# pcb_univ_3-101-0-x-rev2.net
KiCad netlist of a schematic drawn in EAGLE
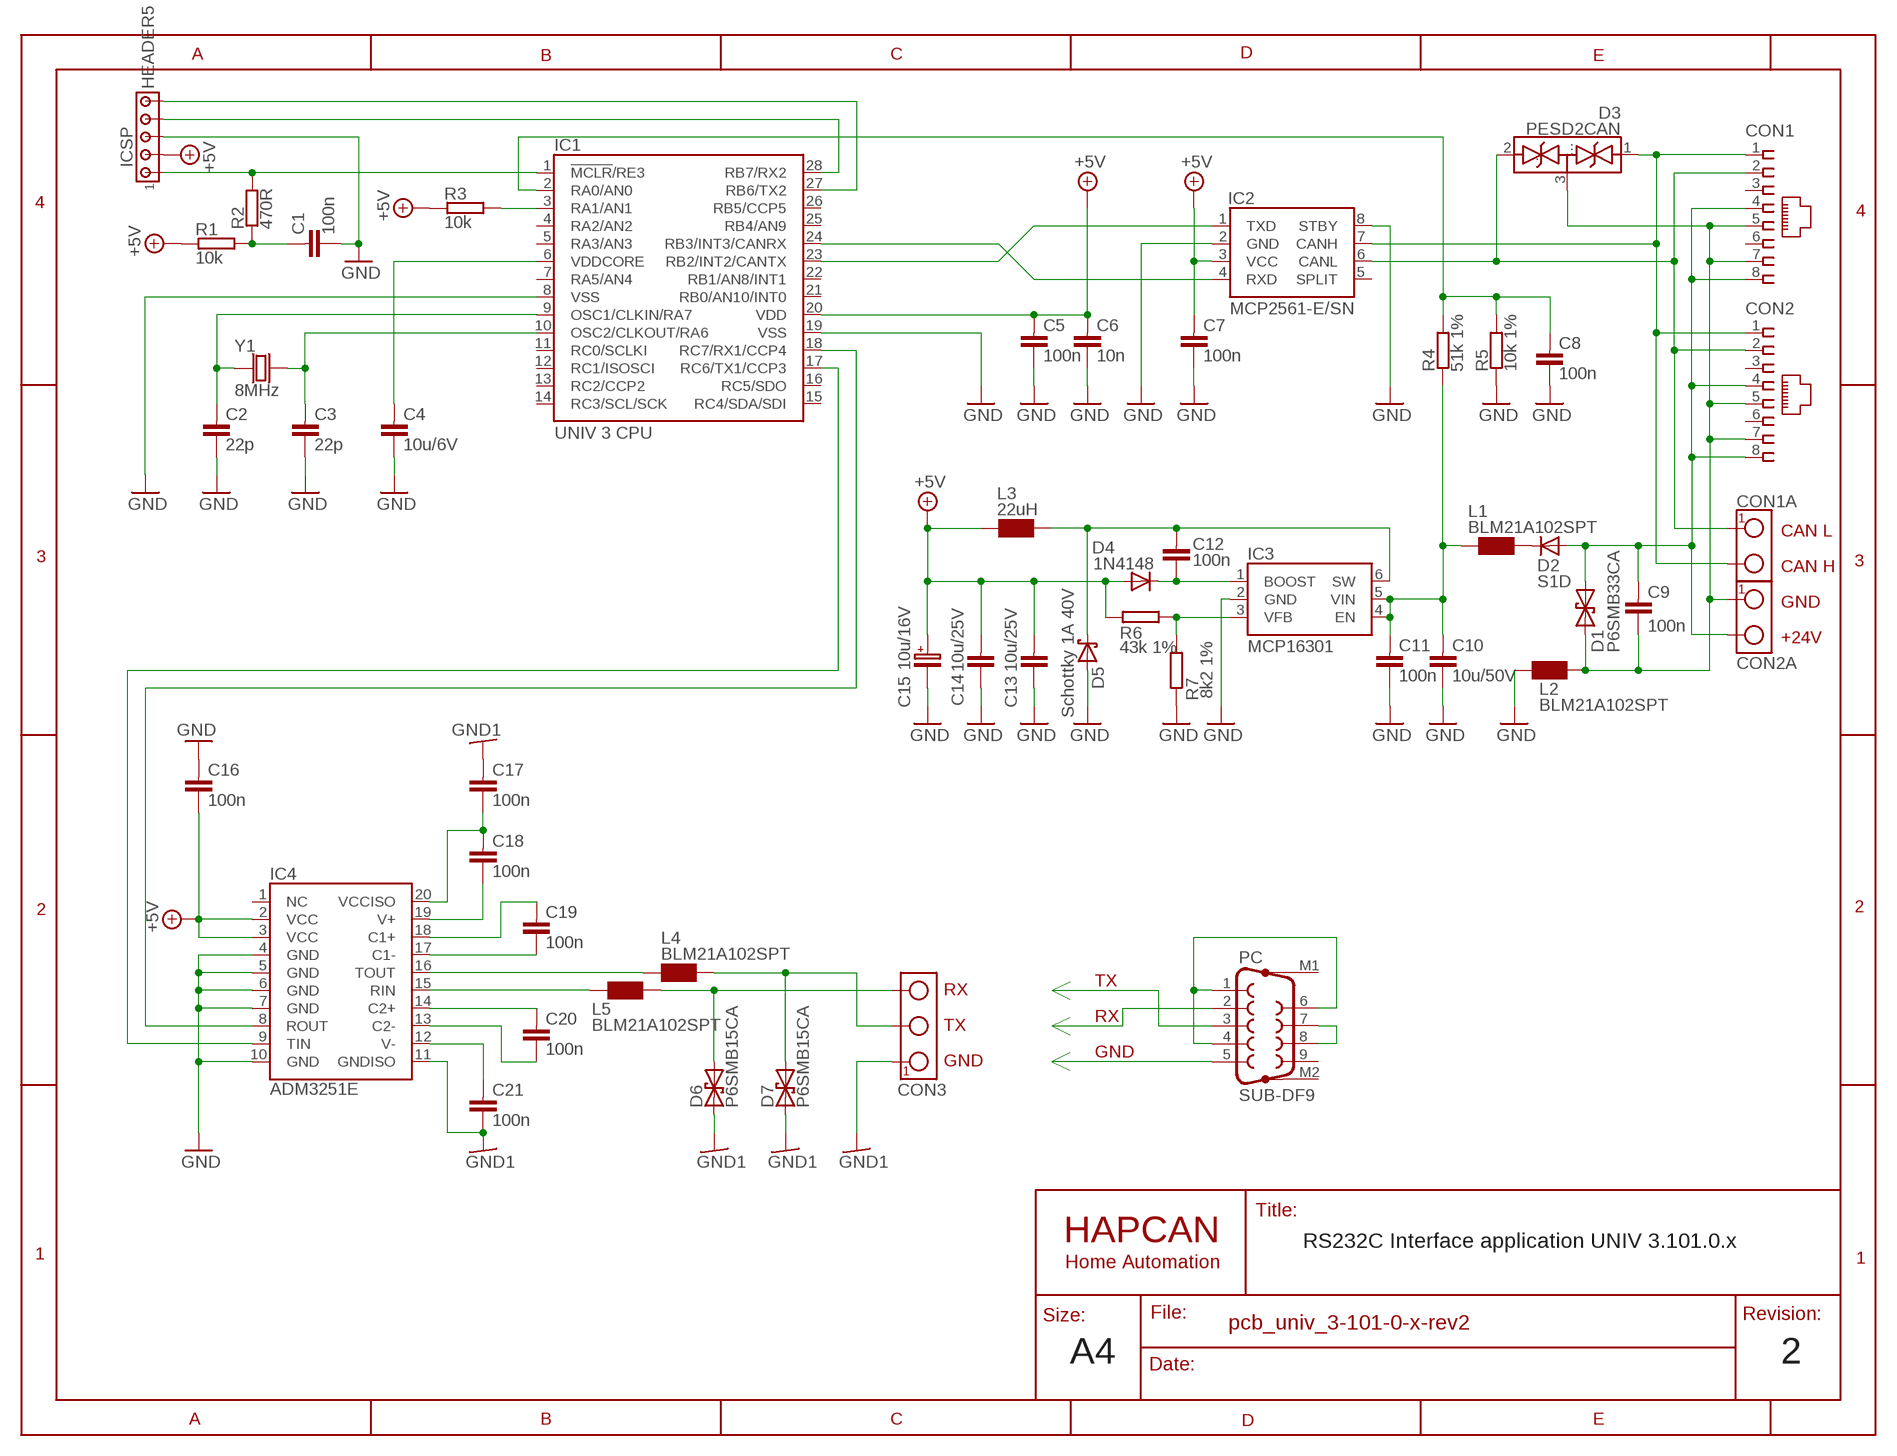
[diagram p0: schematic, sheet 1]

(export (version "E")
  (design (tool "Eeschema 10.0.6"))
  (components
    (comp (ref "C1")
      (value "100n")
      (footprint "eagle-import:0805")
      (libsource (lib "eagle-import") (part "CAPACITOR0805"))
    )
    (comp (ref "C2")
      (value "22p")
      (footprint "eagle-import:0805")
      (libsource (lib "eagle-import") (part "CAPACITOR0805"))
    )
    (comp (ref "C3")
      (value "22p")
      (footprint "eagle-import:0805")
      (libsource (lib "eagle-import") (part "CAPACITOR0805"))
    )
    (comp (ref "C4")
      (value "10u/6V")
      (footprint "eagle-import:0805")
      (libsource (lib "eagle-import") (part "CAPACITOR0805"))
    )
    (comp (ref "C5")
      (value "100n")
      (footprint "eagle-import:0805")
      (libsource (lib "eagle-import") (part "CAPACITOR0805"))
    )
    (comp (ref "C6")
      (value "10n")
      (footprint "eagle-import:0805")
      (libsource (lib "eagle-import") (part "CAPACITOR0805"))
    )
    (comp (ref "C7")
      (value "100n")
      (footprint "eagle-import:0805")
      (libsource (lib "eagle-import") (part "CAPACITOR0805"))
    )
    (comp (ref "C8")
      (value "100n")
      (footprint "eagle-import:0805")
      (libsource (lib "eagle-import") (part "CAPACITOR0805"))
    )
    (comp (ref "C9")
      (value "100n")
      (footprint "eagle-import:0805")
      (libsource (lib "eagle-import") (part "CAPACITOR0805"))
    )
    (comp (ref "C10")
      (value "10u/50V")
      (footprint "eagle-import:1210")
      (libsource (lib "eagle-import") (part "CAPACITOR1210"))
    )
    (comp (ref "C11")
      (value "100n")
      (footprint "eagle-import:0805")
      (libsource (lib "eagle-import") (part "CAPACITOR0805"))
    )
    (comp (ref "C12")
      (value "100n")
      (footprint "eagle-import:0805")
      (libsource (lib "eagle-import") (part "CAPACITOR0805"))
    )
    (comp (ref "C13")
      (value "10u/25V")
      (footprint "eagle-import:1206")
      (libsource (lib "eagle-import") (part "CAPACITOR1206"))
    )
    (comp (ref "C14")
      (value "10u/25V")
      (footprint "eagle-import:1206")
      (libsource (lib "eagle-import") (part "CAPACITOR1206"))
    )
    (comp (ref "C15")
      (value "10u/16V")
      (footprint "eagle-import:SMC_B")
      (libsource (lib "eagle-import") (part "CAPACITOR-POLARIZED-SMC_B"))
    )
    (comp (ref "C16")
      (value "100n")
      (footprint "eagle-import:0805")
      (libsource (lib "eagle-import") (part "CAPACITOR0805"))
    )
    (comp (ref "C17")
      (value "100n")
      (footprint "eagle-import:0805")
      (libsource (lib "eagle-import") (part "CAPACITOR0805"))
    )
    (comp (ref "C18")
      (value "100n")
      (footprint "eagle-import:0805")
      (libsource (lib "eagle-import") (part "CAPACITOR0805"))
    )
    (comp (ref "C19")
      (value "100n")
      (footprint "eagle-import:0805")
      (libsource (lib "eagle-import") (part "CAPACITOR0805"))
    )
    (comp (ref "C20")
      (value "100n")
      (footprint "eagle-import:0805")
      (libsource (lib "eagle-import") (part "CAPACITOR0805"))
    )
    (comp (ref "C21")
      (value "100n")
      (footprint "eagle-import:0805")
      (libsource (lib "eagle-import") (part "CAPACITOR0805"))
    )
    (comp (ref "CON1")
      (value "RJ45-SOCKET")
      (footprint "eagle-import:RJ45-PCB-SOCKET")
      (libsource (lib "eagle-import") (part "RJ45-SOCKET"))
    )
    (comp (ref "CON1A")
      (value "TERMINAL-2")
      (footprint "eagle-import:ARK2-5X10,5MM")
      (libsource (lib "eagle-import") (part "TERMINAL-2-5X10,5MM"))
    )
    (comp (ref "CON2")
      (value "RJ45-SOCKET")
      (footprint "eagle-import:RJ45-PCB-SOCKET")
      (libsource (lib "eagle-import") (part "RJ45-SOCKET"))
    )
    (comp (ref "CON2A")
      (value "TERMINAL-2")
      (footprint "eagle-import:ARK2-5X10,5MM")
      (libsource (lib "eagle-import") (part "TERMINAL-2-5X10,5MM"))
    )
    (comp (ref "CON3")
      (value "TERMINAL-3-5X10.5MM")
      (footprint "eagle-import:ARK3-5X10.5MM")
      (libsource (lib "eagle-import") (part "TERMINAL-3-5X10.5MM"))
    )
    (comp (ref "D1")
      (value "P6SMB33CA")
      (footprint "eagle-import:DO-214_TRANSIL2")
      (libsource (lib "eagle-import") (part "DIODE_TRANSIL2"))
    )
    (comp (ref "D2")
      (value "S1D")
      (footprint "eagle-import:DO-214")
      (libsource (lib "eagle-import") (part "DIODE_DO-214"))
    )
    (comp (ref "D3")
      (value "PESD2CAN")
      (footprint "eagle-import:SOT-23")
      (libsource (lib "eagle-import") (part "PESD2CANSOT-23"))
    )
    (comp (ref "D4")
      (value "1N4148")
      (footprint "eagle-import:0805")
      (libsource (lib "eagle-import") (part "DIODE_0805"))
    )
    (comp (ref "D5")
      (value "Schottky 1A 40V")
      (footprint "eagle-import:DO-214")
      (libsource (lib "eagle-import") (part "DIODE_TRANSIL1_DO214"))
    )
    (comp (ref "D6")
      (value "P6SMB15CA")
      (footprint "eagle-import:DO-214_TRANSIL2")
      (libsource (lib "eagle-import") (part "DIODE_TRANSIL2"))
    )
    (comp (ref "D7")
      (value "P6SMB15CA")
      (footprint "eagle-import:DO-214_TRANSIL2")
      (libsource (lib "eagle-import") (part "DIODE_TRANSIL2"))
    )
    (comp (ref "IC1")
      (value "UNIV 3 CPU")
      (footprint "eagle-import:UNIV3CPU")
      (libsource (lib "eagle-import") (part "UNIV3CPU-I/SO"))
    )
    (comp (ref "IC2")
      (value "MCP2561-E/SN")
      (footprint "eagle-import:SO-08")
      (libsource (lib "eagle-import") (part "MCP2561-E/SN"))
    )
    (comp (ref "IC3")
      (value "MCP16301")
      (footprint "eagle-import:SOT-23-6")
      (libsource (lib "eagle-import") (part "MCP16301SOT23-6"))
    )
    (comp (ref "IC4")
      (value "ADM3251E")
      (footprint "eagle-import:SO-20W")
      (libsource (lib "eagle-import") (part "ADM3251E"))
    )
    (comp (ref "ICSP")
      (value "HEADER5")
      (footprint "eagle-import:SIP-5")
      (libsource (lib "eagle-import") (part "HEADER5"))
    )
    (comp (ref "L1")
      (value "BLM21A102SPT")
      (footprint "eagle-import:0805")
      (libsource (lib "eagle-import") (part "CHOKE0805"))
    )
    (comp (ref "L2")
      (value "BLM21A102SPT")
      (footprint "eagle-import:0805")
      (libsource (lib "eagle-import") (part "CHOKE0805"))
    )
    (comp (ref "L3")
      (value "22uH")
      (footprint "eagle-import:CHOKE-DER0705")
      (libsource (lib "eagle-import") (part "CHOKEDER0705"))
    )
    (comp (ref "L4")
      (value "BLM21A102SPT")
      (footprint "eagle-import:0805")
      (libsource (lib "eagle-import") (part "CHOKE0805"))
    )
    (comp (ref "L5")
      (value "BLM21A102SPT")
      (footprint "eagle-import:0805")
      (libsource (lib "eagle-import") (part "CHOKE0805"))
    )
    (comp (ref "PC")
      (value "SUB-DF9")
      (footprint "eagle-import:SUB-D9FH-7.2MM")
      (libsource (lib "eagle-import") (part "SUB-DF9"))
    )
    (comp (ref "R1")
      (value "10k")
      (footprint "eagle-import:0805")
      (libsource (lib "eagle-import") (part "RESISTOR0805"))
    )
    (comp (ref "R2")
      (value "470R")
      (footprint "eagle-import:0805")
      (libsource (lib "eagle-import") (part "RESISTOR0805"))
    )
    (comp (ref "R3")
      (value "10k")
      (footprint "eagle-import:0805")
      (libsource (lib "eagle-import") (part "RESISTOR0805"))
    )
    (comp (ref "R4")
      (value "51k 1%")
      (footprint "eagle-import:0805")
      (libsource (lib "eagle-import") (part "RESISTOR0805"))
    )
    (comp (ref "R5")
      (value "10k 1%")
      (footprint "eagle-import:0805")
      (libsource (lib "eagle-import") (part "RESISTOR0805"))
    )
    (comp (ref "R6")
      (value "43k 1%")
      (footprint "eagle-import:0805")
      (libsource (lib "eagle-import") (part "RESISTOR0805"))
    )
    (comp (ref "R7")
      (value "8k2 1%")
      (footprint "eagle-import:0805")
      (libsource (lib "eagle-import") (part "RESISTOR0805"))
    )
    (comp (ref "Y1")
      (value "8MHz")
      (footprint "eagle-import:CRYSTAL-HC49V")
      (libsource (lib "eagle-import") (part "CRYSTAL-HC49V"))
    )
  )
  (nets
    (net (code "1") (name "+5V") (class "Default")
      (node (ref "C13") (pin "1") (pinfunction "1_1") (pintype "passive"))
      (node (ref "C14") (pin "1") (pinfunction "1_1") (pintype "passive"))
      (node (ref "C15") (pin "+") (pinfunction "1_+") (pintype "passive"))
      (node (ref "C16") (pin "2") (pinfunction "2_2") (pintype "passive"))
      (node (ref "C5") (pin "1") (pinfunction "1_1") (pintype "passive"))
      (node (ref "C6") (pin "1") (pinfunction "1_1") (pintype "passive"))
      (node (ref "C7") (pin "1") (pinfunction "1_1") (pintype "passive"))
      (node (ref "D4") (pin "2") (pinfunction "A_2") (pintype "passive"))
      (node (ref "IC1") (pin "20") (pinfunction "VDD_20") (pintype "bidirectional"))
      (node (ref "IC2") (pin "3") (pinfunction "VCC_3") (pintype "bidirectional"))
      (node (ref "IC4") (pin "2") (pinfunction "VCC_2") (pintype "bidirectional"))
      (node (ref "IC4") (pin "3") (pinfunction "VCC_3") (pintype "bidirectional"))
      (node (ref "ICSP") (pin "2") (pinfunction "2_2") (pintype "passive"))
      (node (ref "L3") (pin "1") (pinfunction "1_1") (pintype "passive"))
      (node (ref "R1") (pin "1") (pinfunction "1_1") (pintype "passive"))
      (node (ref "R3") (pin "1") (pinfunction "1_1") (pintype "passive"))
      (node (ref "R6") (pin "1") (pinfunction "1_1") (pintype "passive"))
    )
    (net (code "2") (name "GND") (class "Default")
      (node (ref "C1") (pin "2") (pinfunction "2_2") (pintype "passive"))
      (node (ref "C10") (pin "2") (pinfunction "2_2") (pintype "passive"))
      (node (ref "C11") (pin "2") (pinfunction "2_2") (pintype "passive"))
      (node (ref "C13") (pin "2") (pinfunction "2_2") (pintype "passive"))
      (node (ref "C14") (pin "2") (pinfunction "2_2") (pintype "passive"))
      (node (ref "C15") (pin "-") (pinfunction "2_-") (pintype "passive"))
      (node (ref "C16") (pin "1") (pinfunction "1_1") (pintype "passive"))
      (node (ref "C2") (pin "2") (pinfunction "2_2") (pintype "passive"))
      (node (ref "C3") (pin "2") (pinfunction "2_2") (pintype "passive"))
      (node (ref "C4") (pin "2") (pinfunction "2_2") (pintype "passive"))
      (node (ref "C5") (pin "2") (pinfunction "2_2") (pintype "passive"))
      (node (ref "C6") (pin "2") (pinfunction "2_2") (pintype "passive"))
      (node (ref "C7") (pin "2") (pinfunction "2_2") (pintype "passive"))
      (node (ref "C8") (pin "2") (pinfunction "2_2") (pintype "passive"))
      (node (ref "D5") (pin "A") (pinfunction "A_A") (pintype "passive"))
      (node (ref "IC1") (pin "19") (pinfunction "VSS_19") (pintype "bidirectional"))
      (node (ref "IC1") (pin "8") (pinfunction "VSS_8") (pintype "bidirectional"))
      (node (ref "IC2") (pin "2") (pinfunction "GND_2") (pintype "bidirectional"))
      (node (ref "IC2") (pin "8") (pinfunction "STBY_8") (pintype "bidirectional"))
      (node (ref "IC3") (pin "2") (pinfunction "GND_2") (pintype "bidirectional"))
      (node (ref "IC4") (pin "10") (pinfunction "GND_10") (pintype "bidirectional"))
      (node (ref "IC4") (pin "4") (pinfunction "GND_4") (pintype "bidirectional"))
      (node (ref "IC4") (pin "5") (pinfunction "GND_5") (pintype "bidirectional"))
      (node (ref "IC4") (pin "6") (pinfunction "GND_6") (pintype "bidirectional"))
      (node (ref "IC4") (pin "7") (pinfunction "GND_7") (pintype "bidirectional"))
      (node (ref "ICSP") (pin "3") (pinfunction "3_3") (pintype "passive"))
      (node (ref "L2") (pin "1") (pinfunction "1_1") (pintype "passive"))
      (node (ref "R5") (pin "1") (pinfunction "1_1") (pintype "passive"))
      (node (ref "R7") (pin "1") (pinfunction "1_1") (pintype "passive"))
    )
    (net (code "3") (name "GND1") (class "Default")
      (node (ref "C17") (pin "1") (pinfunction "1_1") (pintype "passive"))
      (node (ref "C21") (pin "2") (pinfunction "2_2") (pintype "passive"))
      (node (ref "CON3") (pin "1") (pinfunction "1_1") (pintype "passive"))
      (node (ref "D6") (pin "C") (pinfunction "2_C") (pintype "passive"))
      (node (ref "D7") (pin "C") (pinfunction "2_C") (pintype "passive"))
      (node (ref "IC4") (pin "11") (pinfunction "GNDISO_11") (pintype "bidirectional"))
    )
    (net (code "4") (name "Net-(C1-Pad1)") (class "Default")
      (node (ref "C1") (pin "1") (pinfunction "1_1") (pintype "passive"))
      (node (ref "R1") (pin "2") (pinfunction "2_2") (pintype "passive"))
      (node (ref "R2") (pin "1") (pinfunction "1_1") (pintype "passive"))
    )
    (net (code "5") (name "Net-(D1-1)") (class "Default")
      (node (ref "C9") (pin "1") (pinfunction "1_1") (pintype "passive"))
      (node (ref "CON1") (pin "4") (pinfunction "4_4") (pintype "passive"))
      (node (ref "CON1") (pin "8") (pinfunction "8_8") (pintype "passive"))
      (node (ref "CON2") (pin "4") (pinfunction "4_4") (pintype "passive"))
      (node (ref "CON2") (pin "8") (pinfunction "8_8") (pintype "passive"))
      (node (ref "CON2A") (pin "2") (pinfunction "2_2") (pintype "passive"))
      (node (ref "D1") (pin "A") (pinfunction "1_A") (pintype "passive"))
      (node (ref "D2") (pin "A") (pinfunction "A_A") (pintype "passive"))
    )
    (net (code "6") (name "Net-(D1-2)") (class "Default")
      (node (ref "C9") (pin "2") (pinfunction "2_2") (pintype "passive"))
      (node (ref "CON1") (pin "5") (pinfunction "5_5") (pintype "passive"))
      (node (ref "CON1") (pin "7") (pinfunction "7_7") (pintype "passive"))
      (node (ref "CON2") (pin "5") (pinfunction "5_5") (pintype "passive"))
      (node (ref "CON2") (pin "7") (pinfunction "7_7") (pintype "passive"))
      (node (ref "CON2A") (pin "1") (pinfunction "1_1") (pintype "passive"))
      (node (ref "D1") (pin "C") (pinfunction "2_C") (pintype "passive"))
      (node (ref "D3") (pin "3") (pinfunction "..._3") (pintype "bidirectional"))
      (node (ref "L2") (pin "2") (pinfunction "2_2") (pintype "passive"))
    )
    (net (code "7") (name "Net-(D2-PadC)") (class "Default")
      (node (ref "D2") (pin "C") (pinfunction "C_C") (pintype "passive"))
      (node (ref "L1") (pin "2") (pinfunction "2_2") (pintype "passive"))
    )
    (net (code "8") (name "Net-(D3-.)") (class "Default")
      (node (ref "CON1") (pin "1") (pinfunction "1_1") (pintype "passive"))
      (node (ref "CON1A") (pin "2") (pinfunction "2_2") (pintype "passive"))
      (node (ref "CON2") (pin "1") (pinfunction "1_1") (pintype "passive"))
      (node (ref "D3") (pin "1") (pinfunction "._1") (pintype "bidirectional"))
      (node (ref "IC2") (pin "7") (pinfunction "CANH_7") (pintype "bidirectional"))
    )
    (net (code "9") (name "Net-(D3-..)") (class "Default")
      (node (ref "CON1") (pin "2") (pinfunction "2_2") (pintype "passive"))
      (node (ref "CON1A") (pin "1") (pinfunction "1_1") (pintype "passive"))
      (node (ref "CON2") (pin "2") (pinfunction "2_2") (pintype "passive"))
      (node (ref "D3") (pin "2") (pinfunction ".._2") (pintype "bidirectional"))
      (node (ref "IC2") (pin "6") (pinfunction "CANL_6") (pintype "bidirectional"))
    )
    (net (code "10") (name "Net-(D4-C)") (class "Default")
      (node (ref "C12") (pin "2") (pinfunction "2_2") (pintype "passive"))
      (node (ref "D4") (pin "1") (pinfunction "C_1") (pintype "passive"))
      (node (ref "IC3") (pin "1") (pinfunction "BOOST_1") (pintype "bidirectional"))
    )
    (net (code "11") (name "Net-(D6-1)") (class "Default")
      (node (ref "CON3") (pin "3") (pinfunction "3_3") (pintype "passive"))
      (node (ref "D6") (pin "A") (pinfunction "1_A") (pintype "passive"))
      (node (ref "L5") (pin "1") (pinfunction "1_1") (pintype "passive"))
    )
    (net (code "12") (name "Net-(D7-1)") (class "Default")
      (node (ref "CON3") (pin "2") (pinfunction "2_2") (pintype "passive"))
      (node (ref "D7") (pin "A") (pinfunction "1_A") (pintype "passive"))
      (node (ref "L4") (pin "1") (pinfunction "1_1") (pintype "passive"))
    )
    (net (code "13") (name "Net-(IC1-OSC1{slash}CLKIN{slash}RA7)") (class "Default")
      (node (ref "C2") (pin "1") (pinfunction "1_1") (pintype "passive"))
      (node (ref "IC1") (pin "9") (pinfunction "OSC1/CLKIN/RA7_9") (pintype "bidirectional"))
      (node (ref "Y1") (pin "1") (pinfunction "1_1") (pintype "passive"))
    )
    (net (code "14") (name "Net-(IC1-OSC2{slash}CLKOUT{slash}RA6)") (class "Default")
      (node (ref "C3") (pin "1") (pinfunction "1_1") (pintype "passive"))
      (node (ref "IC1") (pin "10") (pinfunction "OSC2/CLKOUT/RA6_10") (pintype "bidirectional"))
      (node (ref "Y1") (pin "2") (pinfunction "2_2") (pintype "passive"))
    )
    (net (code "15") (name "Net-(IC1-RA0{slash}AN0)") (class "Default")
      (node (ref "C8") (pin "1") (pinfunction "1_1") (pintype "passive"))
      (node (ref "IC1") (pin "2") (pinfunction "RA0/AN0_2") (pintype "bidirectional"))
      (node (ref "R4") (pin "2") (pinfunction "2_2") (pintype "passive"))
      (node (ref "R5") (pin "2") (pinfunction "2_2") (pintype "passive"))
    )
    (net (code "16") (name "Net-(IC1-RA1{slash}AN1)") (class "Default")
      (node (ref "IC1") (pin "3") (pinfunction "RA1/AN1_3") (pintype "bidirectional"))
      (node (ref "R3") (pin "2") (pinfunction "2_2") (pintype "passive"))
    )
    (net (code "17") (name "Net-(IC1-RB2{slash}INT2{slash}CANTX)") (class "Default")
      (node (ref "IC1") (pin "23") (pinfunction "RB2/INT2/CANTX_23") (pintype "bidirectional"))
      (node (ref "IC2") (pin "1") (pinfunction "TXD_1") (pintype "bidirectional"))
    )
    (net (code "18") (name "Net-(IC1-RB3{slash}INT3{slash}CANRX)") (class "Default")
      (node (ref "IC1") (pin "24") (pinfunction "RB3/INT3/CANRX_24") (pintype "bidirectional"))
      (node (ref "IC2") (pin "4") (pinfunction "RXD_4") (pintype "bidirectional"))
    )
    (net (code "19") (name "Net-(IC1-RB6{slash}TX2)") (class "Default")
      (node (ref "IC1") (pin "27") (pinfunction "RB6/TX2_27") (pintype "bidirectional"))
      (node (ref "ICSP") (pin "5") (pinfunction "5_5") (pintype "passive"))
    )
    (net (code "20") (name "Net-(IC1-RB7{slash}RX2)") (class "Default")
      (node (ref "IC1") (pin "28") (pinfunction "RB7/RX2_28") (pintype "bidirectional"))
      (node (ref "ICSP") (pin "4") (pinfunction "4_4") (pintype "passive"))
    )
    (net (code "21") (name "Net-(IC1-RC6{slash}TX1{slash}CCP3)") (class "Default")
      (node (ref "IC1") (pin "17") (pinfunction "RC6/TX1/CCP3_17") (pintype "bidirectional"))
      (node (ref "IC4") (pin "9") (pinfunction "TIN_9") (pintype "bidirectional"))
    )
    (net (code "22") (name "Net-(IC1-RC7{slash}RX1{slash}CCP4)") (class "Default")
      (node (ref "IC1") (pin "18") (pinfunction "RC7/RX1/CCP4_18") (pintype "bidirectional"))
      (node (ref "IC4") (pin "8") (pinfunction "ROUT_8") (pintype "bidirectional"))
    )
    (net (code "23") (name "Net-(IC1-VDDCORE)") (class "Default")
      (node (ref "C4") (pin "1") (pinfunction "1_1") (pintype "passive"))
      (node (ref "IC1") (pin "6") (pinfunction "VDDCORE_6") (pintype "bidirectional"))
    )
    (net (code "24") (name "Net-(IC1-~{MCLR}{slash}RE3)") (class "Default")
      (node (ref "IC1") (pin "1") (pinfunction "~{MCLR}/RE3_1") (pintype "bidirectional"))
      (node (ref "ICSP") (pin "1") (pinfunction "1_1") (pintype "passive"))
      (node (ref "R2") (pin "2") (pinfunction "2_2") (pintype "passive"))
    )
    (net (code "25") (name "Net-(IC3-EN)") (class "Default")
      (node (ref "C10") (pin "1") (pinfunction "1_1") (pintype "passive"))
      (node (ref "C11") (pin "1") (pinfunction "1_1") (pintype "passive"))
      (node (ref "IC3") (pin "4") (pinfunction "EN_4") (pintype "bidirectional"))
      (node (ref "IC3") (pin "5") (pinfunction "VIN_5") (pintype "bidirectional"))
      (node (ref "L1") (pin "1") (pinfunction "1_1") (pintype "passive"))
      (node (ref "R4") (pin "1") (pinfunction "1_1") (pintype "passive"))
    )
    (net (code "26") (name "Net-(IC3-SW)") (class "Default")
      (node (ref "C12") (pin "1") (pinfunction "1_1") (pintype "passive"))
      (node (ref "D5") (pin "C") (pinfunction "C_C") (pintype "passive"))
      (node (ref "IC3") (pin "6") (pinfunction "SW_6") (pintype "bidirectional"))
      (node (ref "L3") (pin "2") (pinfunction "2_2") (pintype "passive"))
    )
    (net (code "27") (name "Net-(IC3-VFB)") (class "Default")
      (node (ref "IC3") (pin "3") (pinfunction "VFB_3") (pintype "bidirectional"))
      (node (ref "R6") (pin "2") (pinfunction "2_2") (pintype "passive"))
      (node (ref "R7") (pin "2") (pinfunction "2_2") (pintype "passive"))
    )
    (net (code "28") (name "Net-(IC4-C1+)") (class "Default")
      (node (ref "C19") (pin "1") (pinfunction "1_1") (pintype "passive"))
      (node (ref "IC4") (pin "18") (pinfunction "C1+_18") (pintype "bidirectional"))
    )
    (net (code "29") (name "Net-(IC4-C1-)") (class "Default")
      (node (ref "C19") (pin "2") (pinfunction "2_2") (pintype "passive"))
      (node (ref "IC4") (pin "17") (pinfunction "C1-_17") (pintype "bidirectional"))
    )
    (net (code "30") (name "Net-(IC4-C2+)") (class "Default")
      (node (ref "C20") (pin "1") (pinfunction "1_1") (pintype "passive"))
      (node (ref "IC4") (pin "14") (pinfunction "C2+_14") (pintype "bidirectional"))
    )
    (net (code "31") (name "Net-(IC4-C2-)") (class "Default")
      (node (ref "C20") (pin "2") (pinfunction "2_2") (pintype "passive"))
      (node (ref "IC4") (pin "13") (pinfunction "C2-_13") (pintype "bidirectional"))
    )
    (net (code "32") (name "Net-(IC4-RIN)") (class "Default")
      (node (ref "IC4") (pin "15") (pinfunction "RIN_15") (pintype "bidirectional"))
      (node (ref "L5") (pin "2") (pinfunction "2_2") (pintype "passive"))
    )
    (net (code "33") (name "Net-(IC4-TOUT)") (class "Default")
      (node (ref "IC4") (pin "16") (pinfunction "TOUT_16") (pintype "bidirectional"))
      (node (ref "L4") (pin "2") (pinfunction "2_2") (pintype "passive"))
    )
    (net (code "34") (name "Net-(IC4-V+)") (class "Default")
      (node (ref "C18") (pin "2") (pinfunction "2_2") (pintype "passive"))
      (node (ref "IC4") (pin "19") (pinfunction "V+_19") (pintype "bidirectional"))
    )
    (net (code "35") (name "Net-(IC4-V-)") (class "Default")
      (node (ref "C21") (pin "1") (pinfunction "1_1") (pintype "passive"))
      (node (ref "IC4") (pin "12") (pinfunction "V-_12") (pintype "bidirectional"))
    )
    (net (code "36") (name "Net-(IC4-VCCISO)") (class "Default")
      (node (ref "C17") (pin "2") (pinfunction "2_2") (pintype "passive"))
      (node (ref "C18") (pin "1") (pinfunction "1_1") (pintype "passive"))
      (node (ref "IC4") (pin "20") (pinfunction "VCCISO_20") (pintype "bidirectional"))
    )
    (net (code "37") (name "Net-(PC-Pad1)") (class "Default")
      (node (ref "PC") (pin "1") (pinfunction "1_1") (pintype "passive"))
      (node (ref "PC") (pin "4") (pinfunction "4_4") (pintype "passive"))
      (node (ref "PC") (pin "6") (pinfunction "6_6") (pintype "passive"))
    )
    (net (code "38") (name "Net-(PC-Pad7)") (class "Default")
      (node (ref "PC") (pin "7") (pinfunction "7_7") (pintype "passive"))
      (node (ref "PC") (pin "8") (pinfunction "8_8") (pintype "passive"))
    )
    (net (code "39") (name "unconnected-(CON1-Pad3)") (class "Default")
      (node (ref "CON1") (pin "3") (pinfunction "3_3") (pintype "passive"))
    )
    (net (code "40") (name "unconnected-(CON1-Pad6)") (class "Default")
      (node (ref "CON1") (pin "6") (pinfunction "6_6") (pintype "passive"))
    )
    (net (code "41") (name "unconnected-(CON2-Pad3)") (class "Default")
      (node (ref "CON2") (pin "3") (pinfunction "3_3") (pintype "passive"))
    )
    (net (code "42") (name "unconnected-(CON2-Pad6)") (class "Default")
      (node (ref "CON2") (pin "6") (pinfunction "6_6") (pintype "passive"))
    )
    (net (code "43") (name "unconnected-(IC1-RA2{slash}AN2-Pad4)") (class "Default")
      (node (ref "IC1") (pin "4") (pinfunction "RA2/AN2_4") (pintype "bidirectional"))
    )
    (net (code "44") (name "unconnected-(IC1-RA3{slash}AN3-Pad5)") (class "Default")
      (node (ref "IC1") (pin "5") (pinfunction "RA3/AN3_5") (pintype "bidirectional"))
    )
    (net (code "45") (name "unconnected-(IC1-RA5{slash}AN4-Pad7)") (class "Default")
      (node (ref "IC1") (pin "7") (pinfunction "RA5/AN4_7") (pintype "bidirectional"))
    )
    (net (code "46") (name "unconnected-(IC1-RB0{slash}AN10{slash}INT0-Pad21)") (class "Default")
      (node (ref "IC1") (pin "21") (pinfunction "RB0/AN10/INT0_21") (pintype "bidirectional"))
    )
    (net (code "47") (name "unconnected-(IC1-RB1{slash}AN8{slash}INT1-Pad22)") (class "Default")
      (node (ref "IC1") (pin "22") (pinfunction "RB1/AN8/INT1_22") (pintype "bidirectional"))
    )
    (net (code "48") (name "unconnected-(IC1-RB4{slash}AN9-Pad25)") (class "Default")
      (node (ref "IC1") (pin "25") (pinfunction "RB4/AN9_25") (pintype "bidirectional"))
    )
    (net (code "49") (name "unconnected-(IC1-RB5{slash}CCP5-Pad26)") (class "Default")
      (node (ref "IC1") (pin "26") (pinfunction "RB5/CCP5_26") (pintype "bidirectional"))
    )
    (net (code "50") (name "unconnected-(IC1-RC0{slash}SCLKI-Pad11)") (class "Default")
      (node (ref "IC1") (pin "11") (pinfunction "RC0/SCLKI_11") (pintype "bidirectional"))
    )
    (net (code "51") (name "unconnected-(IC1-RC1{slash}ISOSCI-Pad12)") (class "Default")
      (node (ref "IC1") (pin "12") (pinfunction "RC1/ISOSCI_12") (pintype "bidirectional"))
    )
    (net (code "52") (name "unconnected-(IC1-RC2{slash}CCP2-Pad13)") (class "Default")
      (node (ref "IC1") (pin "13") (pinfunction "RC2/CCP2_13") (pintype "bidirectional"))
    )
    (net (code "53") (name "unconnected-(IC1-RC3{slash}SCL{slash}SCK-Pad14)") (class "Default")
      (node (ref "IC1") (pin "14") (pinfunction "RC3/SCL/SCK_14") (pintype "bidirectional"))
    )
    (net (code "54") (name "unconnected-(IC1-RC4{slash}SDA{slash}SDI-Pad15)") (class "Default")
      (node (ref "IC1") (pin "15") (pinfunction "RC4/SDA/SDI_15") (pintype "bidirectional"))
    )
    (net (code "55") (name "unconnected-(IC1-RC5{slash}SDO-Pad16)") (class "Default")
      (node (ref "IC1") (pin "16") (pinfunction "RC5/SDO_16") (pintype "bidirectional"))
    )
    (net (code "56") (name "unconnected-(IC2-SPLIT-Pad5)") (class "Default")
      (node (ref "IC2") (pin "5") (pinfunction "SPLIT_5") (pintype "bidirectional"))
    )
    (net (code "57") (name "unconnected-(IC4-NC-Pad1)") (class "Default")
      (node (ref "IC4") (pin "1") (pinfunction "NC_1") (pintype "bidirectional"))
    )
    (net (code "58") (name "unconnected-(PC-G1-PadM1)") (class "Default")
      (node (ref "PC") (pin "M1") (pinfunction "G1_M1") (pintype "passive"))
    )
    (net (code "59") (name "unconnected-(PC-G2-PadM2)") (class "Default")
      (node (ref "PC") (pin "M2") (pinfunction "G2_M2") (pintype "passive"))
    )
    (net (code "60") (name "unconnected-(PC-Pad2)") (class "Default")
      (node (ref "PC") (pin "2") (pinfunction "2_2") (pintype "passive"))
    )
    (net (code "61") (name "unconnected-(PC-Pad3)") (class "Default")
      (node (ref "PC") (pin "3") (pinfunction "3_3") (pintype "passive"))
    )
    (net (code "62") (name "unconnected-(PC-Pad5)") (class "Default")
      (node (ref "PC") (pin "5") (pinfunction "5_5") (pintype "passive"))
    )
    (net (code "63") (name "unconnected-(PC-Pad9)") (class "Default")
      (node (ref "PC") (pin "9") (pinfunction "9_9") (pintype "passive"))
    )
  )
)
